# Sheet2.net
KiCad netlist of a schematic drawn in Altium Designer
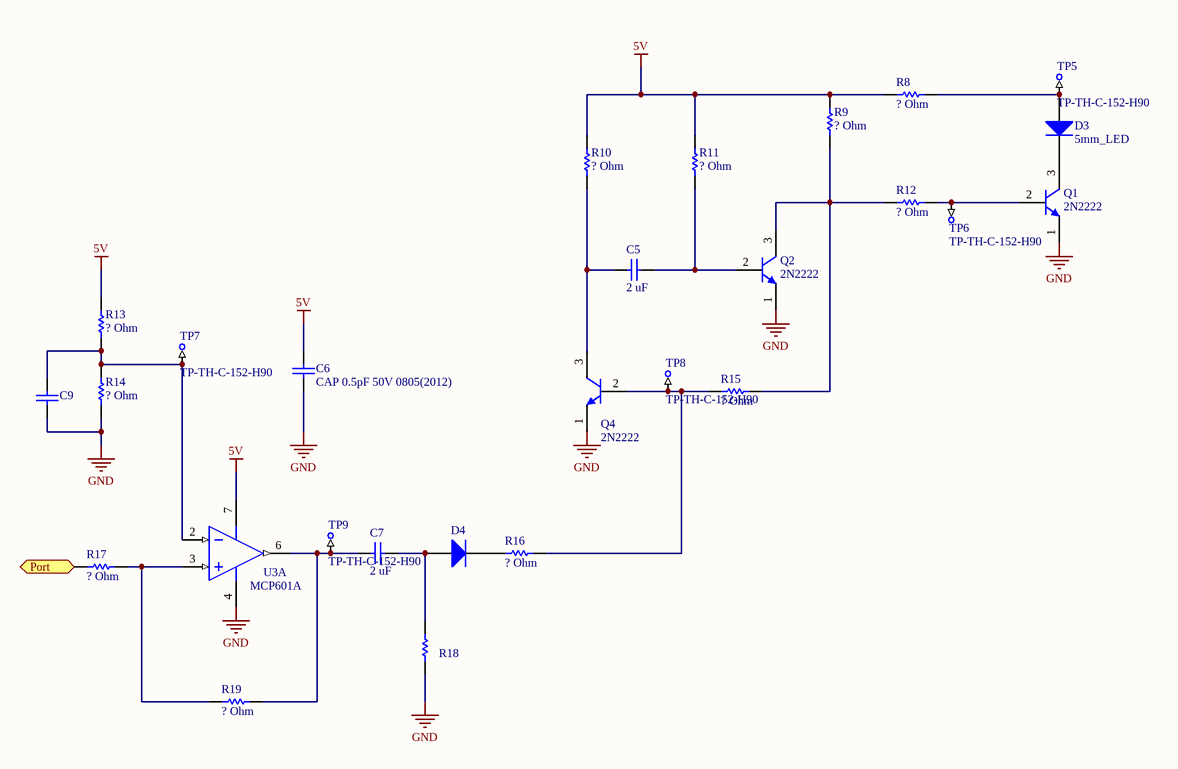
[diagram p0: Sheet2.SchDoc]

(export (version "E")
  (design (tool "Eeschema 10.0.6"))
  (components
    (comp (ref "C5")
      (value "2 uF")
      (footprint "CAPC0805(2012)75_M")
      (description "CAP 0.5pF 50V ±0.1pF 0805 (2012 Metric) Thickness 0.75mm SMD")
      (fields (field (name "TOLERANCE") "Â±0.1pF"))
      (libsource (lib "Altium Content Vault") (part "CAP"))
    )
    (comp (ref "C6")
      (value "CAP 0.5pF 50V 0805(2012)")
      (footprint "CAPC0805(2012)75_M")
      (description "CAP 0.5pF 50V ±0.1pF 0805 (2012 Metric) Thickness 0.75mm SMD")
      (fields (field (name "TOLERANCE") "Â±0.1pF"))
      (libsource (lib "Altium Content Vault") (part "CAP"))
    )
    (comp (ref "C7")
      (value "2 uF")
      (footprint "CAPC0805(2012)75_M")
      (description "CAP 0.5pF 50V ±0.1pF 0805 (2012 Metric) Thickness 0.75mm SMD")
      (fields (field (name "TOLERANCE") "Â±0.1pF"))
      (libsource (lib "Altium Content Vault") (part "CAP"))
    )
    (comp (ref "C9")
      (value "CAP 0.5pF 50V 0805(2012)")
      (footprint "CAPC0805(2012)75_M")
      (description "CAP 0.5pF 50V ±0.1pF 0805 (2012 Metric) Thickness 0.75mm SMD")
      (fields (field (name "TOLERANCE") "Â±0.1pF"))
      (libsource (lib "Altium Content Vault") (part "CMP-1036-00018-1"))
    )
    (comp (ref "D3")
      (value "5mm_LED")
      (footprint "3mm_diode")
      (libsource (lib "HeartbeatLibrary") (part "5mm_LED"))
    )
    (comp (ref "D4")
      (value "~")
      (footprint "DIOD-S1M-13-F-SMA-2_V")
      (fields (field (name "MANUFACTURER") "Diodes Inc") (field (name "PARTNUMBER") "S1M-13-F"))
      (libsource (lib "Altium Content Vault") (part "DIOD-D-A1K2-2"))
    )
    (comp (ref "Q1")
      (value "2N2222")
      (footprint "MLTC-TO-18-3")
      (description "Low Power Bipolar NPN Transistor, 30 V, -65 to 200 degC, 3-Pin TO-18, RoHS, Bulk")
      (fields (field (name "MANUFACTURER") "Multicomp"))
      (libsource (lib "Altium Content Vault") (part "BJT-NPN-EBC-3"))
    )
    (comp (ref "Q2")
      (value "2N2222")
      (footprint "MLTC-TO-18-3")
      (description "Low Power Bipolar NPN Transistor, 30 V, -65 to 200 degC, 3-Pin TO-18, RoHS, Bulk")
      (fields (field (name "MANUFACTURER") "Multicomp"))
      (libsource (lib "Altium Content Vault") (part "BJT-NPN-EBC-3"))
    )
    (comp (ref "Q4")
      (value "2N2222")
      (footprint "MLTC-TO-18-3")
      (description "Low Power Bipolar NPN Transistor, 30 V, -65 to 200 degC, 3-Pin TO-18, RoHS, Bulk")
      (fields (field (name "MANUFACTURER") "Multicomp"))
      (libsource (lib "Altium Content Vault") (part "BJT-NPN-EBC-3"))
    )
    (comp (ref "R8")
      (value "? Ohm")
      (footprint "RESC0805(2012)_M")
      (description "4R3 0.125W 5% 0805 (2012 Metric)  SMD")
      (fields (field (name "TOLERANCE") "5 %") (field (name "POWER") "0.125 W"))
      (libsource (lib "Altium Content Vault") (part "RES"))
    )
    (comp (ref "R9")
      (value "? Ohm")
      (footprint "RESC0805(2012)_M")
      (description "4R3 0.125W 5% 0805 (2012 Metric)  SMD")
      (fields (field (name "TOLERANCE") "5 %") (field (name "POWER") "0.125 W"))
      (libsource (lib "Altium Content Vault") (part "RES"))
    )
    (comp (ref "R10")
      (value "? Ohm")
      (footprint "RESC0805(2012)_M")
      (description "4R3 0.125W 5% 0805 (2012 Metric)  SMD")
      (fields (field (name "TOLERANCE") "5 %") (field (name "POWER") "0.125 W"))
      (libsource (lib "Altium Content Vault") (part "CMP-1013-00017-1"))
    )
    (comp (ref "R11")
      (value "? Ohm")
      (footprint "RESC0805(2012)_M")
      (description "4R3 0.125W 5% 0805 (2012 Metric)  SMD")
      (fields (field (name "TOLERANCE") "5 %") (field (name "POWER") "0.125 W"))
      (libsource (lib "Altium Content Vault") (part "RES"))
    )
    (comp (ref "R12")
      (value "? Ohm")
      (footprint "RESC0805(2012)_M")
      (description "4R3 0.125W 5% 0805 (2012 Metric)  SMD")
      (fields (field (name "TOLERANCE") "5 %") (field (name "POWER") "0.125 W"))
      (libsource (lib "Altium Content Vault") (part "RES"))
    )
    (comp (ref "R13")
      (value "? Ohm")
      (footprint "RESC0805(2012)_M")
      (description "4R3 0.125W 5% 0805 (2012 Metric)  SMD")
      (fields (field (name "TOLERANCE") "5 %") (field (name "POWER") "0.125 W"))
      (libsource (lib "Altium Content Vault") (part "RES"))
    )
    (comp (ref "R14")
      (value "? Ohm")
      (footprint "RESC0805(2012)_M")
      (description "4R3 0.125W 5% 0805 (2012 Metric)  SMD")
      (fields (field (name "TOLERANCE") "5 %") (field (name "POWER") "0.125 W"))
      (libsource (lib "Altium Content Vault") (part "RES"))
    )
    (comp (ref "R15")
      (value "? Ohm")
      (footprint "RESC0805(2012)_M")
      (description "4R3 0.125W 5% 0805 (2012 Metric)  SMD")
      (fields (field (name "TOLERANCE") "5 %") (field (name "POWER") "0.125 W"))
      (libsource (lib "Altium Content Vault") (part "RES"))
    )
    (comp (ref "R16")
      (value "? Ohm")
      (footprint "RESC0805(2012)_M")
      (description "4R3 0.125W 5% 0805 (2012 Metric)  SMD")
      (fields (field (name "TOLERANCE") "5 %") (field (name "POWER") "0.125 W"))
      (libsource (lib "Altium Content Vault") (part "CMP-1013-00017-1"))
    )
    (comp (ref "R17")
      (value "? Ohm")
      (footprint "RESC0805(2012)_M")
      (description "4R3 0.125W 5% 0805 (2012 Metric)  SMD")
      (fields (field (name "TOLERANCE") "5 %") (field (name "POWER") "0.125 W"))
      (libsource (lib "Altium Content Vault") (part "RES"))
    )
    (comp (ref "R18")
      (value "~")
      (footprint "RESC0805(2012)_M")
      (description "4R3 0.125W 5% 0805 (2012 Metric)  SMD")
      (fields (field (name "TOLERANCE") "5 %") (field (name "POWER") "0.125 W"))
      (libsource (lib "Altium Content Vault") (part "CMP-1013-00017-1"))
    )
    (comp (ref "R19")
      (value "? Ohm")
      (footprint "RESC0805(2012)_M")
      (description "4R3 0.125W 5% 0805 (2012 Metric)  SMD")
      (fields (field (name "TOLERANCE") "5 %") (field (name "POWER") "0.125 W"))
      (libsource (lib "Altium Content Vault") (part "RES"))
    )
    (comp (ref "TP5")
      (value "TP-TH-C-152-H90")
      (footprint "TP-TH-C-152-H90")
      (description "Test Point, Through Hole, Hole Size 0.9 mm, PCB Mount with Silkscreen Box")
      (fields (field (name "MANUFACTURER") "No Vendor"))
      (libsource (lib "Altium Content Vault") (part "TP-TH"))
    )
    (comp (ref "TP6")
      (value "TP-TH-C-152-H90")
      (footprint "TP-TH-C-152-H90")
      (description "Test Point, Through Hole, Hole Size 0.9 mm, PCB Mount with Silkscreen Box")
      (fields (field (name "MANUFACTURER") "No Vendor"))
      (libsource (lib "Altium Content Vault") (part "TP-TH"))
    )
    (comp (ref "TP7")
      (value "TP-TH-C-152-H90")
      (footprint "TP-TH-C-152-H90")
      (description "Test Point, Through Hole, Hole Size 0.9 mm, PCB Mount with Silkscreen Box")
      (fields (field (name "MANUFACTURER") "No Vendor"))
      (libsource (lib "Altium Content Vault") (part "TP-TH"))
    )
    (comp (ref "TP8")
      (value "TP-TH-C-152-H90")
      (footprint "TP-TH-C-152-H90")
      (description "Test Point, Through Hole, Hole Size 0.9 mm, PCB Mount with Silkscreen Box")
      (fields (field (name "MANUFACTURER") "No Vendor"))
      (libsource (lib "Altium Content Vault") (part "TP-TH"))
    )
    (comp (ref "TP9")
      (value "TP-TH-C-152-H90")
      (footprint "TP-TH-C-152-H90")
      (description "Test Point, Through Hole, Hole Size 0.9 mm, PCB Mount with Silkscreen Box")
      (fields (field (name "MANUFACTURER") "No Vendor"))
      (libsource (lib "Altium Content Vault") (part "TP-TH"))
    )
    (comp (ref "U3")
      (value "MCP601A")
      (footprint "ADI-Q-8")
      (fields
        (field (name "MANUFACTURER") "Analog Devices")
        (field (name "PARTNUMBER") "5962-9459301MPA")
        (field (name "GENERIC PART NUMBER") "AD8001")
      )
      (libsource (lib "Altium Content Vault") (part "ADI-AD_ADA_OPXXXX-X-8"))
    )
  )
  (nets
    (net (code "1") (name "/Port") (class "Default")
      (node (ref "R17") (pin "2") (pinfunction "2_2") (pintype "passive"))
    )
    (net (code "2") (name "5V") (class "Default")
      (node (ref "C6") (pin "2") (pinfunction "2_2") (pintype "passive"))
      (node (ref "R10") (pin "1") (pinfunction "1_1") (pintype "passive"))
      (node (ref "R11") (pin "1") (pinfunction "1_1") (pintype "passive"))
      (node (ref "R13") (pin "2") (pinfunction "2_2") (pintype "passive"))
      (node (ref "R8") (pin "1") (pinfunction "1_1") (pintype "passive"))
      (node (ref "R9") (pin "1") (pinfunction "1_1") (pintype "passive"))
      (node (ref "U3") (pin "7") (pinfunction "+V_7") (pintype "power_in"))
    )
    (net (code "3") (name "GND") (class "Default")
      (node (ref "C6") (pin "1") (pinfunction "1_1") (pintype "passive"))
      (node (ref "C9") (pin "1") (pinfunction "1_1") (pintype "passive"))
      (node (ref "Q1") (pin "1") (pinfunction "E_1") (pintype "passive"))
      (node (ref "Q2") (pin "1") (pinfunction "E_1") (pintype "passive"))
      (node (ref "Q4") (pin "1") (pinfunction "E_1") (pintype "passive"))
      (node (ref "R14") (pin "2") (pinfunction "2_2") (pintype "passive"))
      (node (ref "R18") (pin "2") (pinfunction "2_2") (pintype "passive"))
      (node (ref "U3") (pin "4") (pinfunction "-V_4") (pintype "power_in"))
    )
    (net (code "4") (name "Net-(D3-A)") (class "Default")
      (node (ref "D3") (pin "1") (pinfunction "A_1") (pintype "passive"))
      (node (ref "R8") (pin "2") (pinfunction "2_2") (pintype "passive"))
      (node (ref "TP5") (pin "1") (pinfunction "1_1") (pintype "input"))
    )
    (net (code "5") (name "Net-(D3-K)") (class "Default")
      (node (ref "D3") (pin "2") (pinfunction "K_2") (pintype "passive"))
      (node (ref "Q1") (pin "3") (pinfunction "C_3") (pintype "passive"))
    )
    (net (code "6") (name "Net-(D4-A)") (class "Default")
      (node (ref "C7") (pin "2") (pinfunction "2_2") (pintype "passive"))
      (node (ref "D4") (pin "1") (pinfunction "A_1") (pintype "passive"))
      (node (ref "R18") (pin "1") (pinfunction "1_1") (pintype "passive"))
    )
    (net (code "7") (name "Net-(D4-K)") (class "Default")
      (node (ref "D4") (pin "2") (pinfunction "K_2") (pintype "passive"))
      (node (ref "R16") (pin "1") (pinfunction "1_1") (pintype "passive"))
    )
    (net (code "8") (name "Net-(Q1-B)") (class "Default")
      (node (ref "Q1") (pin "2") (pinfunction "B_2") (pintype "passive"))
      (node (ref "R12") (pin "2") (pinfunction "2_2") (pintype "passive"))
      (node (ref "TP6") (pin "1") (pinfunction "1_1") (pintype "input"))
    )
    (net (code "9") (name "Net-(Q2-B)") (class "Default")
      (node (ref "C5") (pin "1") (pinfunction "1_1") (pintype "passive"))
      (node (ref "Q2") (pin "2") (pinfunction "B_2") (pintype "passive"))
      (node (ref "R11") (pin "2") (pinfunction "2_2") (pintype "passive"))
    )
    (net (code "10") (name "Net-(Q2-C)") (class "Default")
      (node (ref "Q2") (pin "3") (pinfunction "C_3") (pintype "passive"))
      (node (ref "R12") (pin "1") (pinfunction "1_1") (pintype "passive"))
      (node (ref "R15") (pin "2") (pinfunction "2_2") (pintype "passive"))
      (node (ref "R9") (pin "2") (pinfunction "2_2") (pintype "passive"))
    )
    (net (code "11") (name "Net-(Q4-B)") (class "Default")
      (node (ref "Q4") (pin "2") (pinfunction "B_2") (pintype "passive"))
      (node (ref "R15") (pin "1") (pinfunction "1_1") (pintype "passive"))
      (node (ref "R16") (pin "2") (pinfunction "2_2") (pintype "passive"))
      (node (ref "TP8") (pin "1") (pinfunction "1_1") (pintype "input"))
    )
    (net (code "12") (name "Net-(Q4-C)") (class "Default")
      (node (ref "C5") (pin "2") (pinfunction "2_2") (pintype "passive"))
      (node (ref "Q4") (pin "3") (pinfunction "C_3") (pintype "passive"))
      (node (ref "R10") (pin "2") (pinfunction "2_2") (pintype "passive"))
    )
    (net (code "13") (name "Net-(U3A-+IN)") (class "Default")
      (node (ref "R17") (pin "1") (pinfunction "1_1") (pintype "passive"))
      (node (ref "R19") (pin "2") (pinfunction "2_2") (pintype "passive"))
      (node (ref "U3") (pin "3") (pinfunction "+IN_3") (pintype "input"))
    )
    (net (code "14") (name "Net-(U3A--IN)") (class "Default")
      (node (ref "C9") (pin "2") (pinfunction "2_2") (pintype "passive"))
      (node (ref "R13") (pin "1") (pinfunction "1_1") (pintype "passive"))
      (node (ref "R14") (pin "1") (pinfunction "1_1") (pintype "passive"))
      (node (ref "TP7") (pin "1") (pinfunction "1_1") (pintype "input"))
      (node (ref "U3") (pin "2") (pinfunction "-IN_2") (pintype "input"))
    )
    (net (code "15") (name "Net-(U3A-OUT)") (class "Default")
      (node (ref "C7") (pin "1") (pinfunction "1_1") (pintype "passive"))
      (node (ref "R19") (pin "1") (pinfunction "1_1") (pintype "passive"))
      (node (ref "TP9") (pin "1") (pinfunction "1_1") (pintype "input"))
      (node (ref "U3") (pin "6") (pinfunction "OUT_6") (pintype "output"))
    )
  )
)
